# sliderController_V1_1.net
KiCad netlist of a schematic drawn in EAGLE
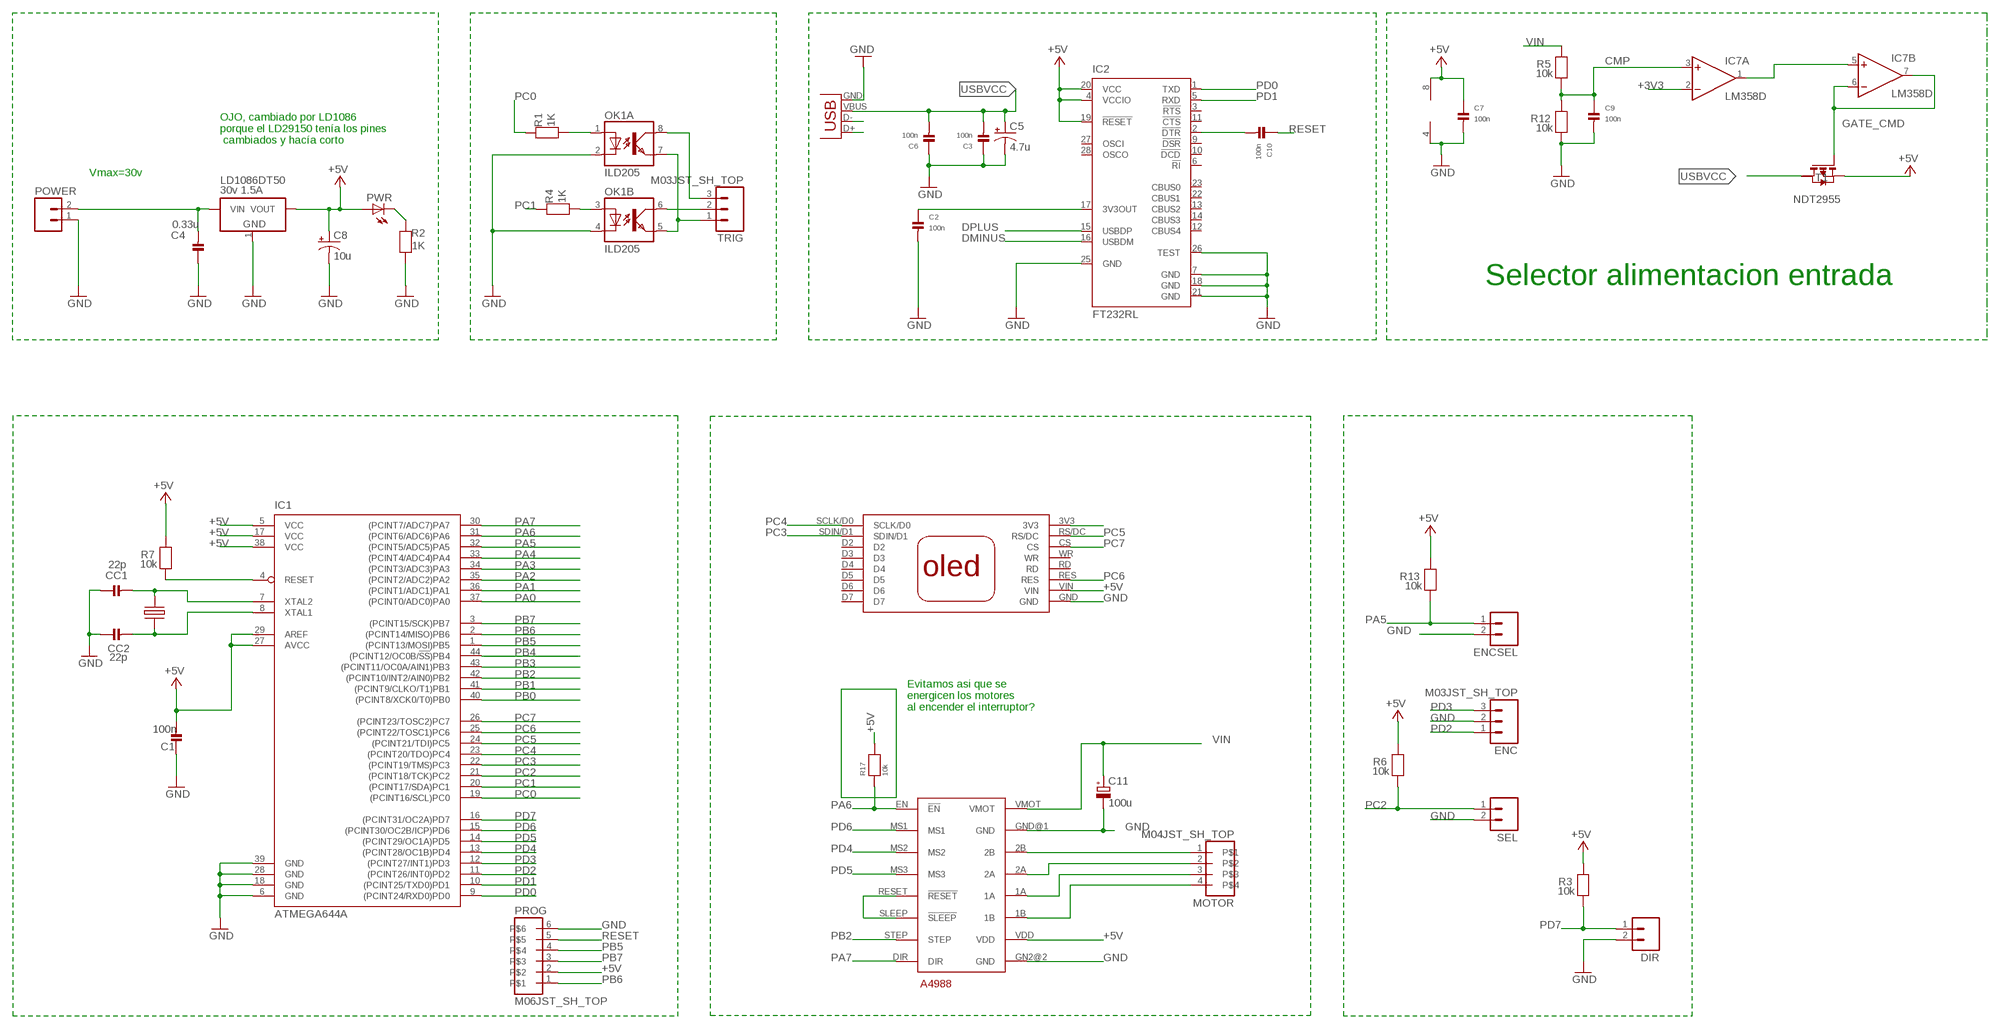
[diagram p0: schematic, sheet 1]

(export (version "E")
  (design (tool "Eeschema 10.0.6"))
  (components
    (comp (ref "A4988")
      (value "STEPSTICK_A4988A4988")
      (footprint "eagle-import:STEPSTICK_A4988")
      (libsource (lib "eagle-import") (part "STEPSTICK_A4988A4988"))
    )
    (comp (ref "C1")
      (value "100n")
      (footprint "eagle-import:_0805")
      (libsource (lib "eagle-import") (part "CAP_CERAMIC_0805"))
    )
    (comp (ref "C2")
      (value "100n")
      (footprint "eagle-import:_0805")
      (libsource (lib "eagle-import") (part "CAP_CERAMIC_0805"))
    )
    (comp (ref "C3")
      (value "100n")
      (footprint "eagle-import:_0805")
      (libsource (lib "eagle-import") (part "CAP_CERAMIC_0805"))
    )
    (comp (ref "C4")
      (value "0.33u")
      (footprint "eagle-import:_0805")
      (libsource (lib "eagle-import") (part "CAP_CERAMIC_0805"))
    )
    (comp (ref "C5")
      (value "4.7u")
      (footprint "eagle-import:EIA3216")
      (libsource (lib "eagle-import") (part "CAP_POL1206"))
    )
    (comp (ref "C6")
      (value "100n")
      (footprint "eagle-import:_0805")
      (libsource (lib "eagle-import") (part "CAP_CERAMIC_0805"))
    )
    (comp (ref "C7")
      (value "100n")
      (footprint "eagle-import:0805")
      (libsource (lib "eagle-import") (part "CAP_CERAMIC0805"))
    )
    (comp (ref "C8")
      (value "10u")
      (footprint "eagle-import:EIA3216")
      (libsource (lib "eagle-import") (part "CAP_POL1206"))
    )
    (comp (ref "C9")
      (value "100n")
      (footprint "eagle-import:0805")
      (libsource (lib "eagle-import") (part "CAP_CERAMIC0805"))
    )
    (comp (ref "C10")
      (value "100n")
      (footprint "eagle-import:_0805")
      (libsource (lib "eagle-import") (part "CAP_CERAMIC_0805"))
    )
    (comp (ref "C11")
      (value "100u")
      (footprint "eagle-import:PANASONIC_D")
      (libsource (lib "eagle-import") (part "CPOL-EUD"))
    )
    (comp (ref "CC1")
      (value "22p")
      (footprint "eagle-import:_0805")
      (libsource (lib "eagle-import") (part "CAP_CERAMIC_0805"))
    )
    (comp (ref "CC2")
      (value "22p")
      (footprint "eagle-import:_0805")
      (libsource (lib "eagle-import") (part "CAP_CERAMIC_0805"))
    )
    (comp (ref "CRISTAL")
      (value "CRISTALSMD")
      (footprint "eagle-import:CRISTAL5X3.2MM")
      (libsource (lib "eagle-import") (part "CRISTALSMD"))
    )
    (comp (ref "DIR")
      (value "M02JST_SH_TOP")
      (footprint "eagle-import:JST_1.0_2_TOP")
      (libsource (lib "eagle-import") (part "M02JST_SH_TOP"))
    )
    (comp (ref "ENC")
      (value "M03JST_SH_TOP")
      (footprint "eagle-import:JST_1.0_3_TOP")
      (libsource (lib "eagle-import") (part "M03JST_SH_TOP"))
    )
    (comp (ref "ENCSEL")
      (value "M02JST_SH_TOP")
      (footprint "eagle-import:JST_1.0_2_TOP")
      (libsource (lib "eagle-import") (part "M02JST_SH_TOP"))
    )
    (comp (ref "IC1")
      (value "ATMEGA644A")
      (footprint "eagle-import:TQFP44")
      (fields (field (name "MPN") "ATMEGA644PV-10AU"))
      (libsource (lib "eagle-import") (part "ATMEGA644A"))
    )
    (comp (ref "IC2")
      (value "FT232RL")
      (footprint "eagle-import:SSOP28")
      (libsource (lib "eagle-import") (part "FT232RL"))
    )
    (comp (ref "IC7")
      (value "LM358D")
      (footprint "eagle-import:SO08")
      (libsource (lib "eagle-import") (part "LM358D"))
    )
    (comp (ref "LD1086DT50")
      (value "30v 1.5A")
      (footprint "eagle-import:DPAK")
      (libsource (lib "eagle-import") (part "VREG_3PINS-DPAK"))
    )
    (comp (ref "MOTOR")
      (value "M04JST_SH_TOP")
      (footprint "eagle-import:JST_1.0_4_TOP")
      (libsource (lib "eagle-import") (part "M04JST_SH_TOP"))
    )
    (comp (ref "OK1")
      (value "ILD205")
      (footprint "eagle-import:SOIC08")
      (fields (field (name "MF") "VISHAY/TELEFUNKEN") (field (name "MPN") "ILD205T"))
      (libsource (lib "eagle-import") (part "ILD205"))
    )
    (comp (ref "POWER")
      (value "M02JST_SH_TOP")
      (footprint "eagle-import:JST_1.0_2_TOP")
      (libsource (lib "eagle-import") (part "M02JST_SH_TOP"))
    )
    (comp (ref "PROG")
      (value "M06JST_SH_TOP")
      (footprint "eagle-import:JST_1.0_6_TOP")
      (libsource (lib "eagle-import") (part "M06JST_SH_TOP"))
    )
    (comp (ref "PWR")
      (value "LEDCHIP-LED0805")
      (footprint "eagle-import:CHIP-LED0805")
      (libsource (lib "eagle-import") (part "LEDCHIP-LED0805"))
    )
    (comp (ref "R1")
      (value "1K")
      (footprint "eagle-import:0805")
      (libsource (lib "eagle-import") (part "RESISTOR0805"))
    )
    (comp (ref "R2")
      (value "1K")
      (footprint "eagle-import:0805")
      (libsource (lib "eagle-import") (part "RESISTOR0805"))
    )
    (comp (ref "R3")
      (value "10k")
      (footprint "eagle-import:0805")
      (libsource (lib "eagle-import") (part "RESISTOR0805"))
    )
    (comp (ref "R4")
      (value "1K")
      (footprint "eagle-import:0805")
      (libsource (lib "eagle-import") (part "RESISTOR0805"))
    )
    (comp (ref "R5")
      (value "10k")
      (footprint "eagle-import:0805")
      (libsource (lib "eagle-import") (part "RESISTOR0805"))
    )
    (comp (ref "R6")
      (value "10k")
      (footprint "eagle-import:0805")
      (libsource (lib "eagle-import") (part "RESISTOR0805"))
    )
    (comp (ref "R7")
      (value "10k")
      (footprint "eagle-import:0805")
      (libsource (lib "eagle-import") (part "RESISTOR0805"))
    )
    (comp (ref "R12")
      (value "10k")
      (footprint "eagle-import:0805")
      (libsource (lib "eagle-import") (part "RESISTOR0805"))
    )
    (comp (ref "R13")
      (value "10k")
      (footprint "eagle-import:0805")
      (libsource (lib "eagle-import") (part "RESISTOR0805"))
    )
    (comp (ref "R17")
      (value "10k")
      (footprint "eagle-import:0805")
      (libsource (lib "eagle-import") (part "RESISTOR0805"))
    )
    (comp (ref "SEL")
      (value "M02JST_SH_TOP")
      (footprint "eagle-import:JST_1.0_2_TOP")
      (libsource (lib "eagle-import") (part "M02JST_SH_TOP"))
    )
    (comp (ref "T1")
      (value "NDT2955")
      (footprint "eagle-import:SOT223")
      (libsource (lib "eagle-import") (part "PMOSSOT223"))
    )
    (comp (ref "TRIG")
      (value "M03JST_SH_TOP")
      (footprint "eagle-import:JST_1.0_3_TOP")
      (libsource (lib "eagle-import") (part "M03JST_SH_TOP"))
    )
    (comp (ref "U$3")
      (value "OLEDOLED1.3\"")
      (footprint "eagle-import:OLED1.3_")
      (libsource (lib "eagle-import") (part "OLEDOLED1.3{dblquote}"))
    )
    (comp (ref "X2")
      (value "USBSMD")
      (footprint "eagle-import:USB-MINIB")
      (libsource (lib "eagle-import") (part "USBSMD"))
    )
  )
  (nets
    (net (code "1") (name "+5V") (class "Default")
      (node (ref "A4988") (pin "VDD") (pinfunction "VDD_VDD") (pintype "bidirectional"))
      (node (ref "C1") (pin "2") (pinfunction "P$2_2") (pintype "passive"))
      (node (ref "C7") (pin "1") (pinfunction "P$1_1") (pintype "passive"))
      (node (ref "C8") (pin "A") (pinfunction "+_A") (pintype "passive"))
      (node (ref "IC1") (pin "17") (pinfunction "VCC_17") (pintype "power_in"))
      (node (ref "IC1") (pin "27") (pinfunction "AVCC_27") (pintype "power_in"))
      (node (ref "IC1") (pin "29") (pinfunction "AREF_29") (pintype "passive"))
      (node (ref "IC1") (pin "38") (pinfunction "VCC_38") (pintype "power_in"))
      (node (ref "IC1") (pin "5") (pinfunction "VCC_5") (pintype "power_in"))
      (node (ref "IC2") (pin "19") (pinfunction "~{RESET}_19") (pintype "input"))
      (node (ref "IC2") (pin "20") (pinfunction "VCC_20") (pintype "power_in"))
      (node (ref "IC2") (pin "4") (pinfunction "VCCIO_4") (pintype "power_in"))
      (node (ref "IC7") (pin "8") (pinfunction "V+_8") (pintype "power_in"))
      (node (ref "LD1086DT50") (pin "2") (pinfunction "VOUT_2") (pintype "bidirectional"))
      (node (ref "PROG") (pin "2") (pinfunction "P$2_2") (pintype "bidirectional"))
      (node (ref "PWR") (pin "A") (pinfunction "A_A") (pintype "passive"))
      (node (ref "R13") (pin "2") (pinfunction "2_2") (pintype "passive"))
      (node (ref "R17") (pin "2") (pinfunction "2_2") (pintype "passive"))
      (node (ref "R3") (pin "2") (pinfunction "2_2") (pintype "passive"))
      (node (ref "R6") (pin "2") (pinfunction "2_2") (pintype "passive"))
      (node (ref "R7") (pin "2") (pinfunction "2_2") (pintype "passive"))
      (node (ref "T1") (pin "3") (pinfunction "S_3") (pintype "passive"))
      (node (ref "U$3") (pin "VIN") (pinfunction "VIN_VIN") (pintype "bidirectional"))
    )
    (net (code "2") (name "/+3V3") (class "Default")
      (node (ref "C2") (pin "1") (pinfunction "P$1_1") (pintype "passive"))
      (node (ref "IC2") (pin "17") (pinfunction "3V3OUT_17") (pintype "output"))
      (node (ref "IC7") (pin "2") (pinfunction "-IN_2") (pintype "input"))
    )
    (net (code "3") (name "/CMP") (class "Default")
      (node (ref "C9") (pin "1") (pinfunction "P$1_1") (pintype "passive"))
      (node (ref "IC7") (pin "3") (pinfunction "+IN_3") (pintype "input"))
      (node (ref "R12") (pin "2") (pinfunction "2_2") (pintype "passive"))
      (node (ref "R5") (pin "1") (pinfunction "1_1") (pintype "passive"))
    )
    (net (code "4") (name "/DMINUS") (class "Default")
      (node (ref "IC2") (pin "16") (pinfunction "USBDM_16") (pintype "bidirectional"))
      (node (ref "X2") (pin "D-") (pinfunction "D-_D-") (pintype "bidirectional"))
    )
    (net (code "5") (name "/DPLUS") (class "Default")
      (node (ref "IC2") (pin "15") (pinfunction "USBDP_15") (pintype "bidirectional"))
      (node (ref "X2") (pin "D+") (pinfunction "D+_D+") (pintype "bidirectional"))
    )
    (net (code "6") (name "/GATE_CMD") (class "Default")
      (node (ref "IC7") (pin "6") (pinfunction "-IN_6") (pintype "input"))
      (node (ref "IC7") (pin "7") (pinfunction "OUT_7") (pintype "output"))
      (node (ref "T1") (pin "1") (pinfunction "G_1") (pintype "passive"))
    )
    (net (code "7") (name "/PA0") (class "Default")
      (node (ref "IC1") (pin "37") (pinfunction "(PCINT0/ADC0)PA0_37") (pintype "bidirectional"))
    )
    (net (code "8") (name "/PA1") (class "Default")
      (node (ref "IC1") (pin "36") (pinfunction "(PCINT1/ADC1)PA1_36") (pintype "bidirectional"))
    )
    (net (code "9") (name "/PA2") (class "Default")
      (node (ref "IC1") (pin "35") (pinfunction "(PCINT2/ADC2)PA2_35") (pintype "bidirectional"))
    )
    (net (code "10") (name "/PA3") (class "Default")
      (node (ref "IC1") (pin "34") (pinfunction "(PCINT3/ADC3)PA3_34") (pintype "bidirectional"))
    )
    (net (code "11") (name "/PA4") (class "Default")
      (node (ref "IC1") (pin "33") (pinfunction "(PCINT4/ADC4)PA4_33") (pintype "bidirectional"))
    )
    (net (code "12") (name "/PA5") (class "Default")
      (node (ref "ENCSEL") (pin "1") (pinfunction "1_1") (pintype "passive"))
      (node (ref "IC1") (pin "32") (pinfunction "(PCINT5/ADC5)PA5_32") (pintype "bidirectional"))
      (node (ref "R13") (pin "1") (pinfunction "1_1") (pintype "passive"))
    )
    (net (code "13") (name "/PA6") (class "Default")
      (node (ref "A4988") (pin "EN") (pinfunction "~{EN}_EN") (pintype "bidirectional"))
      (node (ref "IC1") (pin "31") (pinfunction "(PCINT6/ADC6)PA6_31") (pintype "bidirectional"))
      (node (ref "R17") (pin "1") (pinfunction "1_1") (pintype "passive"))
    )
    (net (code "14") (name "/PA7") (class "Default")
      (node (ref "A4988") (pin "DIR") (pinfunction "DIR_DIR") (pintype "bidirectional"))
      (node (ref "IC1") (pin "30") (pinfunction "(PCINT7/ADC7)PA7_30") (pintype "bidirectional"))
    )
    (net (code "15") (name "/PB0") (class "Default")
      (node (ref "IC1") (pin "40") (pinfunction "(PCINT8/XCK0/T0)PB0_40") (pintype "bidirectional"))
    )
    (net (code "16") (name "/PB1") (class "Default")
      (node (ref "IC1") (pin "41") (pinfunction "(PCINT9/CLKO/T1)PB1_41") (pintype "bidirectional"))
    )
    (net (code "17") (name "/PB2") (class "Default")
      (node (ref "A4988") (pin "STEP") (pinfunction "STEP_STEP") (pintype "bidirectional"))
      (node (ref "IC1") (pin "42") (pinfunction "(PCINT10/INT2/AIN0)PB2_42") (pintype "bidirectional"))
    )
    (net (code "18") (name "/PB3") (class "Default")
      (node (ref "IC1") (pin "43") (pinfunction "(PCINT11/OC0A/AIN1)PB3_43") (pintype "bidirectional"))
    )
    (net (code "19") (name "/PB4") (class "Default")
      (node (ref "IC1") (pin "44") (pinfunction "(PCINT12/OC0B/~{SS})PB4_44") (pintype "bidirectional"))
    )
    (net (code "20") (name "/PB5") (class "Default")
      (node (ref "IC1") (pin "1") (pinfunction "(PCINT13/MOSI)PB5_1") (pintype "bidirectional"))
      (node (ref "PROG") (pin "4") (pinfunction "P$4_4") (pintype "bidirectional"))
    )
    (net (code "21") (name "/PB6") (class "Default")
      (node (ref "IC1") (pin "2") (pinfunction "(PCINT14/MISO)PB6_2") (pintype "bidirectional"))
      (node (ref "PROG") (pin "1") (pinfunction "P$1_1") (pintype "bidirectional"))
    )
    (net (code "22") (name "/PB7") (class "Default")
      (node (ref "IC1") (pin "3") (pinfunction "(PCINT15/SCK)PB7_3") (pintype "bidirectional"))
      (node (ref "PROG") (pin "3") (pinfunction "P$3_3") (pintype "bidirectional"))
    )
    (net (code "23") (name "/PC0") (class "Default")
      (node (ref "IC1") (pin "19") (pinfunction "(PCINT16/SCL)PC0_19") (pintype "output"))
      (node (ref "R1") (pin "1") (pinfunction "1_1") (pintype "passive"))
    )
    (net (code "24") (name "/PC1") (class "Default")
      (node (ref "IC1") (pin "20") (pinfunction "(PCINT17/SDA)PC1_20") (pintype "output"))
      (node (ref "R4") (pin "1") (pinfunction "1_1") (pintype "passive"))
    )
    (net (code "25") (name "/PC2") (class "Default")
      (node (ref "IC1") (pin "21") (pinfunction "(PCINT18/TCK)PC2_21") (pintype "output"))
      (node (ref "R6") (pin "1") (pinfunction "1_1") (pintype "passive"))
      (node (ref "SEL") (pin "1") (pinfunction "1_1") (pintype "passive"))
    )
    (net (code "26") (name "/PC3") (class "Default")
      (node (ref "IC1") (pin "22") (pinfunction "(PCINT19/TMS)PC3_22") (pintype "output"))
      (node (ref "U$3") (pin "SDIN/D1") (pinfunction "SDIN/D1_SDIN/D1") (pintype "bidirectional"))
    )
    (net (code "27") (name "/PC4") (class "Default")
      (node (ref "IC1") (pin "23") (pinfunction "(PCINT20/TDO)PC4_23") (pintype "output"))
      (node (ref "U$3") (pin "SCLK/D0") (pinfunction "SCLK/D0_SCLK/D0") (pintype "bidirectional"))
    )
    (net (code "28") (name "/PC5") (class "Default")
      (node (ref "IC1") (pin "24") (pinfunction "(PCINT21/TDI)PC5_24") (pintype "output"))
      (node (ref "U$3") (pin "RS/DC") (pinfunction "RS/DC_RS/DC") (pintype "bidirectional"))
    )
    (net (code "29") (name "/PC6") (class "Default")
      (node (ref "IC1") (pin "25") (pinfunction "(PCINT22/TOSC1)PC6_25") (pintype "output"))
      (node (ref "U$3") (pin "RES") (pinfunction "RES_RES") (pintype "bidirectional"))
    )
    (net (code "30") (name "/PC7") (class "Default")
      (node (ref "IC1") (pin "26") (pinfunction "(PCINT23/TOSC2)PC7_26") (pintype "output"))
      (node (ref "U$3") (pin "CS") (pinfunction "CS_CS") (pintype "bidirectional"))
    )
    (net (code "31") (name "/PD0") (class "Default")
      (node (ref "IC1") (pin "9") (pinfunction "(PCINT24/RXD0)PD0_9") (pintype "bidirectional"))
      (node (ref "IC2") (pin "1") (pinfunction "TXD_1") (pintype "output"))
    )
    (net (code "32") (name "/PD1") (class "Default")
      (node (ref "IC1") (pin "10") (pinfunction "(PCINT25/TXD0)PD1_10") (pintype "bidirectional"))
      (node (ref "IC2") (pin "5") (pinfunction "RXD_5") (pintype "input"))
    )
    (net (code "33") (name "/PD2") (class "Default")
      (node (ref "ENC") (pin "1") (pinfunction "1_1") (pintype "passive"))
      (node (ref "IC1") (pin "11") (pinfunction "(PCINT26/INT0)PD2_11") (pintype "bidirectional"))
    )
    (net (code "34") (name "/PD3") (class "Default")
      (node (ref "ENC") (pin "3") (pinfunction "3_3") (pintype "passive"))
      (node (ref "IC1") (pin "12") (pinfunction "(PCINT27/INT1)PD3_12") (pintype "bidirectional"))
    )
    (net (code "35") (name "/PD4") (class "Default")
      (node (ref "A4988") (pin "MS2") (pinfunction "MS2_MS2") (pintype "bidirectional"))
      (node (ref "IC1") (pin "13") (pinfunction "(PCINT28/OC1B)PD4_13") (pintype "bidirectional"))
    )
    (net (code "36") (name "/PD5") (class "Default")
      (node (ref "A4988") (pin "MS3") (pinfunction "MS3_MS3") (pintype "bidirectional"))
      (node (ref "IC1") (pin "14") (pinfunction "(PCINT29/OC1A)PD5_14") (pintype "bidirectional"))
    )
    (net (code "37") (name "/PD6") (class "Default")
      (node (ref "A4988") (pin "MS1") (pinfunction "MS1_MS1") (pintype "bidirectional"))
      (node (ref "IC1") (pin "15") (pinfunction "(PCINT30/OC2B/ICP)PD6_15") (pintype "bidirectional"))
    )
    (net (code "38") (name "/PD7") (class "Default")
      (node (ref "DIR") (pin "1") (pinfunction "1_1") (pintype "passive"))
      (node (ref "IC1") (pin "16") (pinfunction "(PCINT31/OC2A)PD7_16") (pintype "bidirectional"))
      (node (ref "R3") (pin "1") (pinfunction "1_1") (pintype "passive"))
    )
    (net (code "39") (name "/RESET") (class "Default")
      (node (ref "C10") (pin "1") (pinfunction "P$1_1") (pintype "passive"))
      (node (ref "IC1") (pin "4") (pinfunction "RESET_4") (pintype "input"))
      (node (ref "PROG") (pin "5") (pinfunction "P$5_5") (pintype "bidirectional"))
      (node (ref "R7") (pin "1") (pinfunction "1_1") (pintype "passive"))
    )
    (net (code "40") (name "/VIN") (class "Default")
      (node (ref "A4988") (pin "VMOT") (pinfunction "VMOT_VMOT") (pintype "bidirectional"))
      (node (ref "C11") (pin "+") (pinfunction "+_+") (pintype "passive"))
      (node (ref "C4") (pin "2") (pinfunction "P$2_2") (pintype "passive"))
      (node (ref "LD1086DT50") (pin "3") (pinfunction "VIN_3") (pintype "bidirectional"))
      (node (ref "POWER") (pin "2") (pinfunction "2_2") (pintype "passive"))
      (node (ref "R5") (pin "2") (pinfunction "2_2") (pintype "passive"))
    )
    (net (code "41") (name "GND") (class "Default")
      (node (ref "A4988") (pin "GN2@2") (pinfunction "GND_GN2@2") (pintype "bidirectional"))
      (node (ref "A4988") (pin "GND@1") (pinfunction "GND_GND@1") (pintype "bidirectional"))
      (node (ref "C1") (pin "1") (pinfunction "P$1_1") (pintype "passive"))
      (node (ref "C11") (pin "-") (pinfunction "-_-") (pintype "passive"))
      (node (ref "C2") (pin "2") (pinfunction "P$2_2") (pintype "passive"))
      (node (ref "C3") (pin "1") (pinfunction "P$1_1") (pintype "passive"))
      (node (ref "C4") (pin "1") (pinfunction "P$1_1") (pintype "passive"))
      (node (ref "C5") (pin "C") (pinfunction "-_C") (pintype "passive"))
      (node (ref "C6") (pin "1") (pinfunction "P$1_1") (pintype "passive"))
      (node (ref "C7") (pin "2") (pinfunction "P$2_2") (pintype "passive"))
      (node (ref "C8") (pin "C") (pinfunction "-_C") (pintype "passive"))
      (node (ref "C9") (pin "2") (pinfunction "P$2_2") (pintype "passive"))
      (node (ref "CC1") (pin "1") (pinfunction "P$1_1") (pintype "passive"))
      (node (ref "CC2") (pin "1") (pinfunction "P$1_1") (pintype "passive"))
      (node (ref "DIR") (pin "2") (pinfunction "2_2") (pintype "passive"))
      (node (ref "ENC") (pin "2") (pinfunction "2_2") (pintype "passive"))
      (node (ref "ENCSEL") (pin "2") (pinfunction "2_2") (pintype "passive"))
      (node (ref "IC1") (pin "18") (pinfunction "GND_18") (pintype "power_in"))
      (node (ref "IC1") (pin "28") (pinfunction "GND_28") (pintype "power_in"))
      (node (ref "IC1") (pin "39") (pinfunction "GND_39") (pintype "power_in"))
      (node (ref "IC1") (pin "6") (pinfunction "GND_6") (pintype "power_in"))
      (node (ref "IC2") (pin "18") (pinfunction "GND_18") (pintype "power_in"))
      (node (ref "IC2") (pin "21") (pinfunction "GND_21") (pintype "power_in"))
      (node (ref "IC2") (pin "25") (pinfunction "GND_25") (pintype "power_in"))
      (node (ref "IC2") (pin "26") (pinfunction "TEST_26") (pintype "input"))
      (node (ref "IC2") (pin "7") (pinfunction "GND_7") (pintype "power_in"))
      (node (ref "IC7") (pin "4") (pinfunction "V-_4") (pintype "power_in"))
      (node (ref "LD1086DT50") (pin "1") (pinfunction "GND_1") (pintype "bidirectional"))
      (node (ref "OK1") (pin "2") (pinfunction "C_2") (pintype "passive"))
      (node (ref "OK1") (pin "4") (pinfunction "C_4") (pintype "passive"))
      (node (ref "POWER") (pin "1") (pinfunction "1_1") (pintype "passive"))
      (node (ref "PROG") (pin "6") (pinfunction "P$6_6") (pintype "bidirectional"))
      (node (ref "R12") (pin "1") (pinfunction "1_1") (pintype "passive"))
      (node (ref "R2") (pin "2") (pinfunction "2_2") (pintype "passive"))
      (node (ref "SEL") (pin "2") (pinfunction "2_2") (pintype "passive"))
      (node (ref "U$3") (pin "GND") (pinfunction "GND_GND") (pintype "bidirectional"))
      (node (ref "X2") (pin "GND") (pinfunction "GND_GND") (pintype "bidirectional"))
    )
    (net (code "42") (name "Net-(A4988-~{RESET})") (class "Default")
      (node (ref "A4988") (pin "RESET") (pinfunction "~{RESET}_RESET") (pintype "bidirectional"))
      (node (ref "A4988") (pin "SLEEP") (pinfunction "~{SLEEP}_SLEEP") (pintype "bidirectional"))
    )
    (net (code "43") (name "Net-(C10-P$2)") (class "Default")
      (node (ref "C10") (pin "2") (pinfunction "P$2_2") (pintype "passive"))
      (node (ref "IC2") (pin "2") (pinfunction "~{DTR}_2") (pintype "output"))
    )
    (net (code "44") (name "Net-(CC1-P$2)") (class "Default")
      (node (ref "CC1") (pin "2") (pinfunction "P$2_2") (pintype "passive"))
      (node (ref "CRISTAL") (pin "B") (pinfunction "P$2_B") (pintype "bidirectional"))
      (node (ref "IC1") (pin "7") (pinfunction "XTAL2_7") (pintype "bidirectional"))
    )
    (net (code "45") (name "Net-(CC2-P$2)") (class "Default")
      (node (ref "CC2") (pin "2") (pinfunction "P$2_2") (pintype "passive"))
      (node (ref "CRISTAL") (pin "A") (pinfunction "P$1_A") (pintype "bidirectional"))
      (node (ref "IC1") (pin "8") (pinfunction "XTAL1_8") (pintype "bidirectional"))
    )
    (net (code "46") (name "Net-(IC7A-OUT)") (class "Default")
      (node (ref "IC7") (pin "1") (pinfunction "OUT_1") (pintype "output"))
      (node (ref "IC7") (pin "5") (pinfunction "+IN_5") (pintype "input"))
    )
    (net (code "47") (name "Net-(MOTOR-P$1)") (class "Default")
      (node (ref "A4988") (pin "2B") (pinfunction "2B_2B") (pintype "bidirectional"))
      (node (ref "MOTOR") (pin "1") (pinfunction "P$1_1") (pintype "bidirectional"))
    )
    (net (code "48") (name "Net-(MOTOR-P$2)") (class "Default")
      (node (ref "A4988") (pin "2A") (pinfunction "2A_2A") (pintype "bidirectional"))
      (node (ref "MOTOR") (pin "2") (pinfunction "P$2_2") (pintype "bidirectional"))
    )
    (net (code "49") (name "Net-(MOTOR-P$3)") (class "Default")
      (node (ref "A4988") (pin "1A") (pinfunction "1A_1A") (pintype "bidirectional"))
      (node (ref "MOTOR") (pin "3") (pinfunction "P$3_3") (pintype "bidirectional"))
    )
    (net (code "50") (name "Net-(MOTOR-P$4)") (class "Default")
      (node (ref "A4988") (pin "1B") (pinfunction "1B_1B") (pintype "bidirectional"))
      (node (ref "MOTOR") (pin "4") (pinfunction "P$4_4") (pintype "bidirectional"))
    )
    (net (code "51") (name "Net-(OK1A-A)") (class "Default")
      (node (ref "OK1") (pin "1") (pinfunction "A_1") (pintype "passive"))
      (node (ref "R1") (pin "2") (pinfunction "2_2") (pintype "passive"))
    )
    (net (code "52") (name "Net-(OK1A-COL)") (class "Default")
      (node (ref "OK1") (pin "8") (pinfunction "COL_8") (pintype "passive"))
      (node (ref "TRIG") (pin "3") (pinfunction "3_3") (pintype "passive"))
    )
    (net (code "53") (name "Net-(OK1A-EMIT)") (class "Default")
      (node (ref "OK1") (pin "5") (pinfunction "EMIT_5") (pintype "passive"))
      (node (ref "OK1") (pin "7") (pinfunction "EMIT_7") (pintype "passive"))
      (node (ref "TRIG") (pin "1") (pinfunction "1_1") (pintype "passive"))
    )
    (net (code "54") (name "Net-(OK1B-A)") (class "Default")
      (node (ref "OK1") (pin "3") (pinfunction "A_3") (pintype "passive"))
      (node (ref "R4") (pin "2") (pinfunction "2_2") (pintype "passive"))
    )
    (net (code "55") (name "Net-(OK1B-COL)") (class "Default")
      (node (ref "OK1") (pin "6") (pinfunction "COL_6") (pintype "passive"))
      (node (ref "TRIG") (pin "2") (pinfunction "2_2") (pintype "passive"))
    )
    (net (code "56") (name "Net-(PWR-PadC)") (class "Default")
      (node (ref "PWR") (pin "C") (pinfunction "C_C") (pintype "passive"))
      (node (ref "R2") (pin "1") (pinfunction "1_1") (pintype "passive"))
    )
    (net (code "57") (name "USBVCC") (class "Default")
      (node (ref "C3") (pin "2") (pinfunction "P$2_2") (pintype "passive"))
      (node (ref "C5") (pin "A") (pinfunction "+_A") (pintype "passive"))
      (node (ref "C6") (pin "2") (pinfunction "P$2_2") (pintype "passive"))
      (node (ref "T1") (pin "2") (pinfunction "D_2") (pintype "passive"))
      (node (ref "X2") (pin "VBUS") (pinfunction "VBUS_VBUS") (pintype "bidirectional"))
    )
    (net (code "58") (name "unconnected-(IC2-CBUS0-Pad23)") (class "Default")
      (node (ref "IC2") (pin "23") (pinfunction "CBUS0_23") (pintype "bidirectional"))
    )
    (net (code "59") (name "unconnected-(IC2-CBUS1-Pad22)") (class "Default")
      (node (ref "IC2") (pin "22") (pinfunction "CBUS1_22") (pintype "bidirectional"))
    )
    (net (code "60") (name "unconnected-(IC2-CBUS2-Pad13)") (class "Default")
      (node (ref "IC2") (pin "13") (pinfunction "CBUS2_13") (pintype "bidirectional"))
    )
    (net (code "61") (name "unconnected-(IC2-CBUS3-Pad14)") (class "Default")
      (node (ref "IC2") (pin "14") (pinfunction "CBUS3_14") (pintype "bidirectional"))
    )
    (net (code "62") (name "unconnected-(IC2-CBUS4-Pad12)") (class "Default")
      (node (ref "IC2") (pin "12") (pinfunction "CBUS4_12") (pintype "bidirectional"))
    )
    (net (code "63") (name "unconnected-(IC2-OSCI-Pad27)") (class "Default")
      (node (ref "IC2") (pin "27") (pinfunction "OSCI_27") (pintype "input"))
    )
    (net (code "64") (name "unconnected-(IC2-OSCO-Pad28)") (class "Default")
      (node (ref "IC2") (pin "28") (pinfunction "OSCO_28") (pintype "output"))
    )
    (net (code "65") (name "unconnected-(IC2-~{CTS}-Pad11)") (class "Default")
      (node (ref "IC2") (pin "11") (pinfunction "~{CTS}_11") (pintype "input"))
    )
    (net (code "66") (name "unconnected-(IC2-~{DCD}-Pad10)") (class "Default")
      (node (ref "IC2") (pin "10") (pinfunction "~{DCD}_10") (pintype "input"))
    )
    (net (code "67") (name "unconnected-(IC2-~{DSR}-Pad9)") (class "Default")
      (node (ref "IC2") (pin "9") (pinfunction "~{DSR}_9") (pintype "input"))
    )
    (net (code "68") (name "unconnected-(IC2-~{RI}-Pad6)") (class "Default")
      (node (ref "IC2") (pin "6") (pinfunction "~{RI}_6") (pintype "input"))
    )
    (net (code "69") (name "unconnected-(IC2-~{RTS}-Pad3)") (class "Default")
      (node (ref "IC2") (pin "3") (pinfunction "~{RTS}_3") (pintype "output"))
    )
    (net (code "70") (name "unconnected-(T1-D2-Pad4)") (class "Default")
      (node (ref "T1") (pin "4") (pinfunction "D2_4") (pintype "passive"))
    )
    (net (code "71") (name "unconnected-(U$3-Pad3V3)") (class "Default")
      (node (ref "U$3") (pin "3V3") (pinfunction "3V3_3V3") (pintype "bidirectional"))
    )
    (net (code "72") (name "unconnected-(U$3-PadD2)") (class "Default")
      (node (ref "U$3") (pin "D2") (pinfunction "D2_D2") (pintype "bidirectional"))
    )
    (net (code "73") (name "unconnected-(U$3-PadD3)") (class "Default")
      (node (ref "U$3") (pin "D3") (pinfunction "D3_D3") (pintype "bidirectional"))
    )
    (net (code "74") (name "unconnected-(U$3-PadD4)") (class "Default")
      (node (ref "U$3") (pin "D4") (pinfunction "D4_D4") (pintype "bidirectional"))
    )
    (net (code "75") (name "unconnected-(U$3-PadD5)") (class "Default")
      (node (ref "U$3") (pin "D5") (pinfunction "D5_D5") (pintype "bidirectional"))
    )
    (net (code "76") (name "unconnected-(U$3-PadD6)") (class "Default")
      (node (ref "U$3") (pin "D6") (pinfunction "D6_D6") (pintype "bidirectional"))
    )
    (net (code "77") (name "unconnected-(U$3-PadD7)") (class "Default")
      (node (ref "U$3") (pin "D7") (pinfunction "D7_D7") (pintype "bidirectional"))
    )
    (net (code "78") (name "unconnected-(U$3-PadRD)") (class "Default")
      (node (ref "U$3") (pin "RD") (pinfunction "RD_RD") (pintype "bidirectional"))
    )
    (net (code "79") (name "unconnected-(U$3-PadWR)") (class "Default")
      (node (ref "U$3") (pin "WR") (pinfunction "WR_WR") (pintype "bidirectional"))
    )
  )
)
